# tsal_1.net
KiCad netlist of a schematic drawn in EAGLE
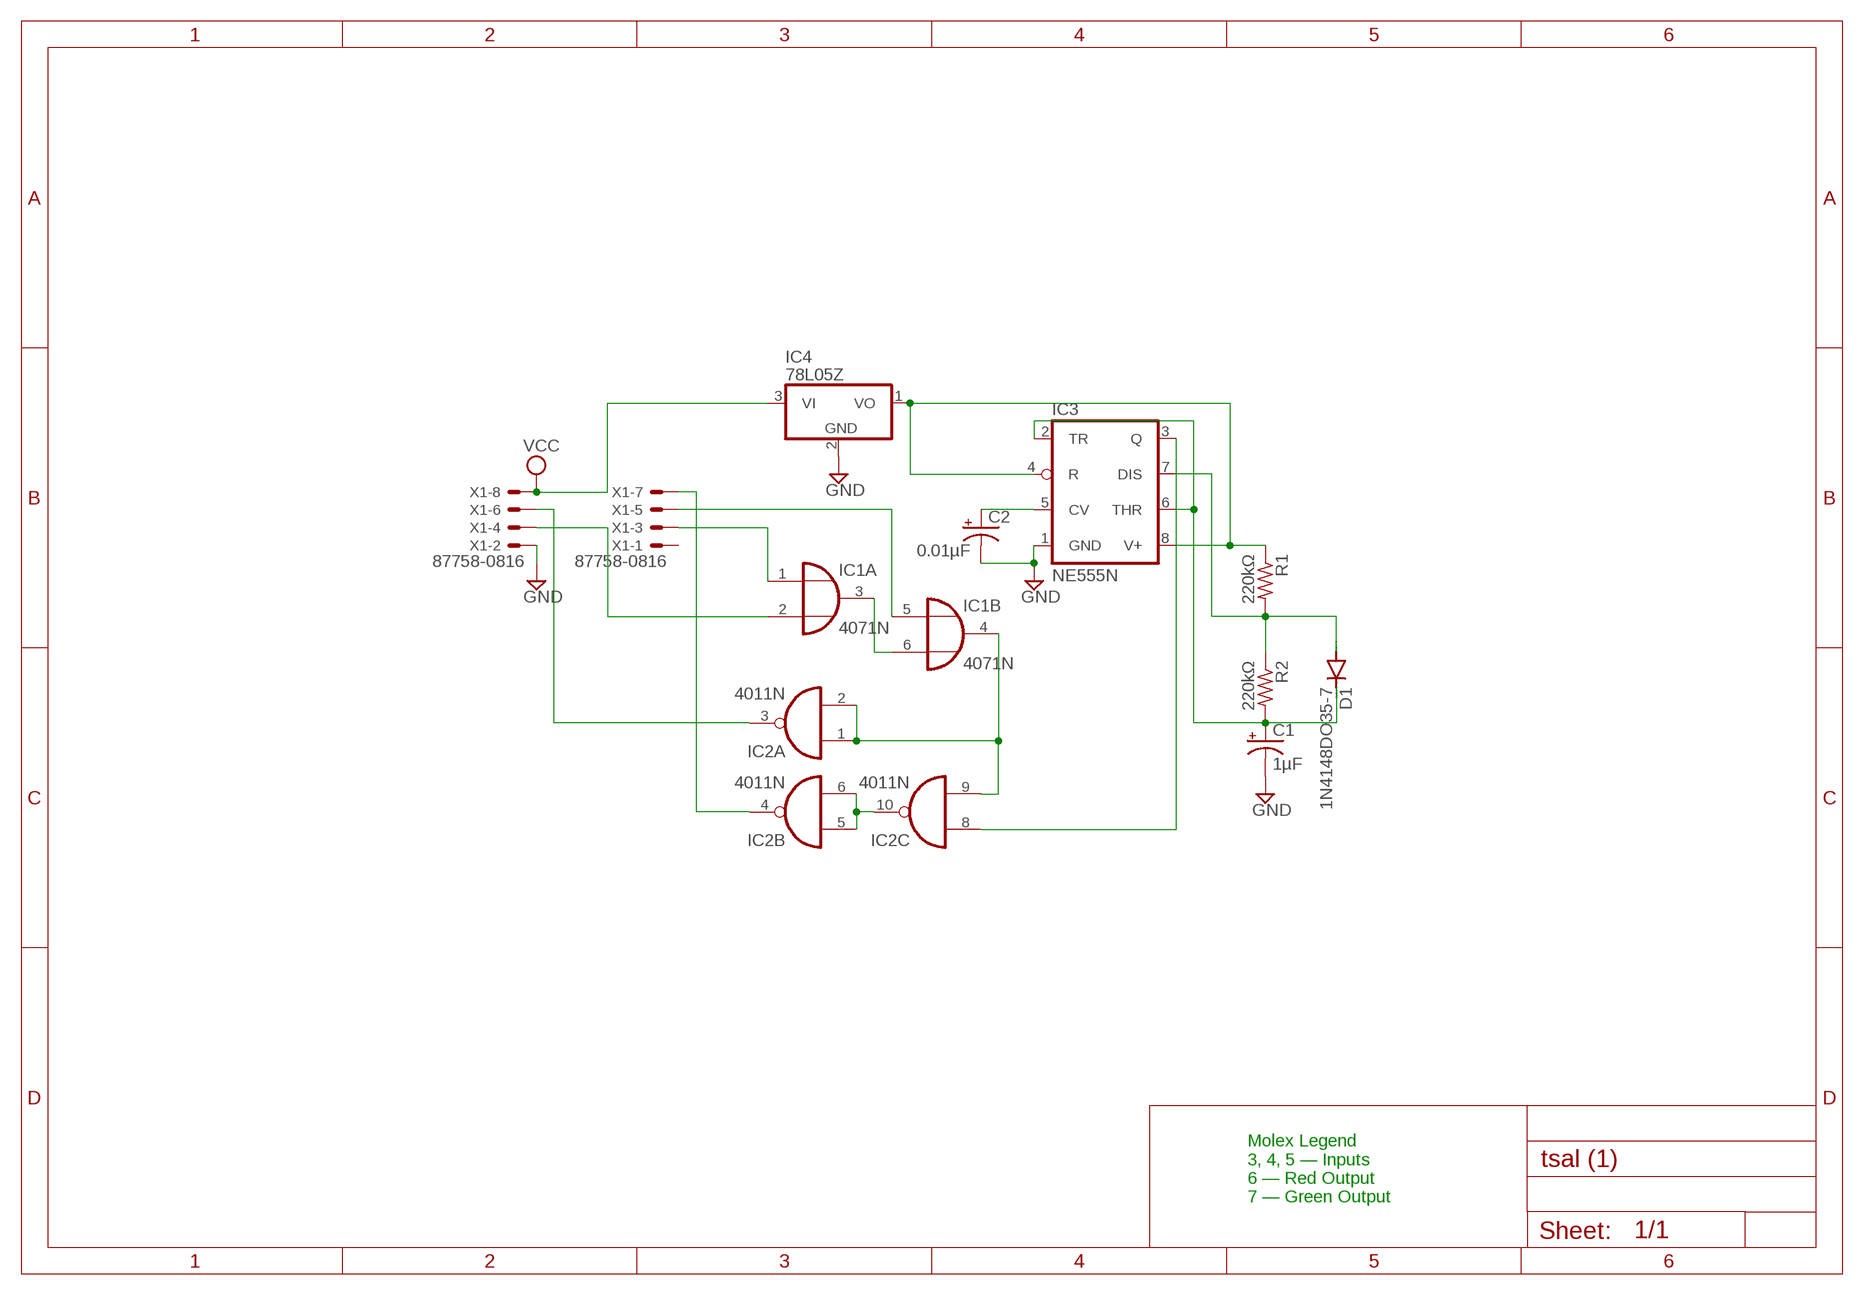
[diagram p0: schematic, sheet 1]

(export (version "E")
  (design (tool "Eeschema 10.0.6"))
  (components
    (comp (ref "C1")
      (value "1µF")
      (footprint "eagle-import:E1,8-4")
      (libsource (lib "eagle-import") (part "CPOL-USE1.8-4"))
    )
    (comp (ref "C2")
      (value "0.01µF")
      (footprint "eagle-import:E1,8-4")
      (libsource (lib "eagle-import") (part "CPOL-USE1.8-4"))
    )
    (comp (ref "D1")
      (value "1N4148DO35-7")
      (footprint "eagle-import:DO35-7")
      (libsource (lib "eagle-import") (part "1N4148DO35-7"))
    )
    (comp (ref "IC1")
      (value "4071N")
      (footprint "eagle-import:DIL14")
      (libsource (lib "eagle-import") (part "4071N"))
    )
    (comp (ref "IC2")
      (value "4011N")
      (footprint "eagle-import:DIL14")
      (libsource (lib "eagle-import") (part "4011N"))
    )
    (comp (ref "IC3")
      (value "NE555N")
      (footprint "eagle-import:DIL08")
      (libsource (lib "eagle-import") (part "555NNE"))
    )
    (comp (ref "IC4")
      (value "78L05Z")
      (footprint "eagle-import:TO92")
      (libsource (lib "eagle-import") (part "78ZL05"))
    )
    (comp (ref "R1")
      (value "220kΩ")
      (footprint "eagle-import:0204_7")
      (libsource (lib "eagle-import") (part "R-US_0204/7"))
    )
    (comp (ref "R2")
      (value "220kΩ")
      (footprint "eagle-import:0204_7")
      (libsource (lib "eagle-import") (part "R-US_0204/7"))
    )
    (comp (ref "X1")
      (value "87758-0816")
      (footprint "eagle-import:87758-0816")
      (fields (field (name "MF") "MOLEX"))
      (libsource (lib "eagle-import") (part "87758-0816"))
    )
  )
  (nets
    (net (code "1") (name "GND") (class "Default")
      (node (ref "C1") (pin "-") (pinfunction "-_-") (pintype "passive"))
      (node (ref "C2") (pin "-") (pinfunction "-_-") (pintype "passive"))
      (node (ref "IC3") (pin "1") (pinfunction "GND_1") (pintype "power_in"))
      (node (ref "IC4") (pin "2") (pinfunction "GND_2") (pintype "passive"))
      (node (ref "X1") (pin "2") (pinfunction "S_2") (pintype "passive"))
    )
    (net (code "2") (name "Net-(IC1A-I0)") (class "Default")
      (node (ref "IC1") (pin "1") (pinfunction "I0_1") (pintype "input"))
      (node (ref "X1") (pin "3") (pinfunction "S_3") (pintype "passive"))
    )
    (net (code "3") (name "Net-(IC1A-I1)") (class "Default")
      (node (ref "IC1") (pin "2") (pinfunction "I1_2") (pintype "input"))
      (node (ref "X1") (pin "4") (pinfunction "S_4") (pintype "passive"))
    )
    (net (code "4") (name "Net-(IC1A-O)") (class "Default")
      (node (ref "IC1") (pin "3") (pinfunction "O_3") (pintype "output"))
      (node (ref "IC1") (pin "6") (pinfunction "I1_6") (pintype "input"))
    )
    (net (code "5") (name "Net-(IC1B-I0)") (class "Default")
      (node (ref "IC1") (pin "5") (pinfunction "I0_5") (pintype "input"))
      (node (ref "X1") (pin "5") (pinfunction "S_5") (pintype "passive"))
    )
    (net (code "6") (name "Net-(IC1B-O)") (class "Default")
      (node (ref "IC1") (pin "4") (pinfunction "O_4") (pintype "output"))
      (node (ref "IC2") (pin "1") (pinfunction "I0_1") (pintype "input"))
      (node (ref "IC2") (pin "2") (pinfunction "I1_2") (pintype "input"))
      (node (ref "IC2") (pin "9") (pinfunction "I1_9") (pintype "input"))
    )
    (net (code "7") (name "Net-(IC2A-O)") (class "Default")
      (node (ref "IC2") (pin "3") (pinfunction "O_3") (pintype "output"))
      (node (ref "X1") (pin "6") (pinfunction "S_6") (pintype "passive"))
    )
    (net (code "8") (name "Net-(IC2B-I0)") (class "Default")
      (node (ref "IC2") (pin "10") (pinfunction "O_10") (pintype "output"))
      (node (ref "IC2") (pin "5") (pinfunction "I0_5") (pintype "input"))
      (node (ref "IC2") (pin "6") (pinfunction "I1_6") (pintype "input"))
    )
    (net (code "9") (name "Net-(IC2B-O)") (class "Default")
      (node (ref "IC2") (pin "4") (pinfunction "O_4") (pintype "output"))
      (node (ref "X1") (pin "7") (pinfunction "S_7") (pintype "passive"))
    )
    (net (code "10") (name "Net-(IC2C-I0)") (class "Default")
      (node (ref "IC2") (pin "8") (pinfunction "I0_8") (pintype "input"))
      (node (ref "IC3") (pin "3") (pinfunction "Q_3") (pintype "output"))
    )
    (net (code "11") (name "Net-(IC3-CV)") (class "Default")
      (node (ref "C2") (pin "+") (pinfunction "+_+") (pintype "passive"))
      (node (ref "IC3") (pin "5") (pinfunction "CV_5") (pintype "input"))
    )
    (net (code "12") (name "Net-(IC3-DIS)") (class "Default")
      (node (ref "D1") (pin "A") (pinfunction "A_A") (pintype "passive"))
      (node (ref "IC3") (pin "7") (pinfunction "DIS_7") (pintype "input"))
      (node (ref "R1") (pin "2") (pinfunction "2_2") (pintype "passive"))
      (node (ref "R2") (pin "1") (pinfunction "1_1") (pintype "passive"))
    )
    (net (code "13") (name "Net-(IC3-R)") (class "Default")
      (node (ref "IC3") (pin "4") (pinfunction "R_4") (pintype "input"))
      (node (ref "IC3") (pin "8") (pinfunction "V+_8") (pintype "power_in"))
      (node (ref "IC4") (pin "1") (pinfunction "VO_1") (pintype "passive"))
      (node (ref "R1") (pin "1") (pinfunction "1_1") (pintype "passive"))
    )
    (net (code "14") (name "Net-(IC3-THR)") (class "Default")
      (node (ref "C1") (pin "+") (pinfunction "+_+") (pintype "passive"))
      (node (ref "D1") (pin "C") (pinfunction "C_C") (pintype "passive"))
      (node (ref "IC3") (pin "2") (pinfunction "TR_2") (pintype "input"))
      (node (ref "IC3") (pin "6") (pinfunction "THR_6") (pintype "input"))
      (node (ref "R2") (pin "2") (pinfunction "2_2") (pintype "passive"))
    )
    (net (code "15") (name "VCC") (class "Default")
      (node (ref "IC4") (pin "3") (pinfunction "VI_3") (pintype "input"))
      (node (ref "X1") (pin "8") (pinfunction "S_8") (pintype "passive"))
    )
    (net (code "16") (name "unconnected-(X1A-S-Pad1)") (class "Default")
      (node (ref "X1") (pin "1") (pinfunction "S_1") (pintype "passive"))
    )
  )
)
